# 17_-_PWR_IN_LEDS_BUTTONS_MECH.net
KiCad netlist of a schematic drawn in Altium Designer
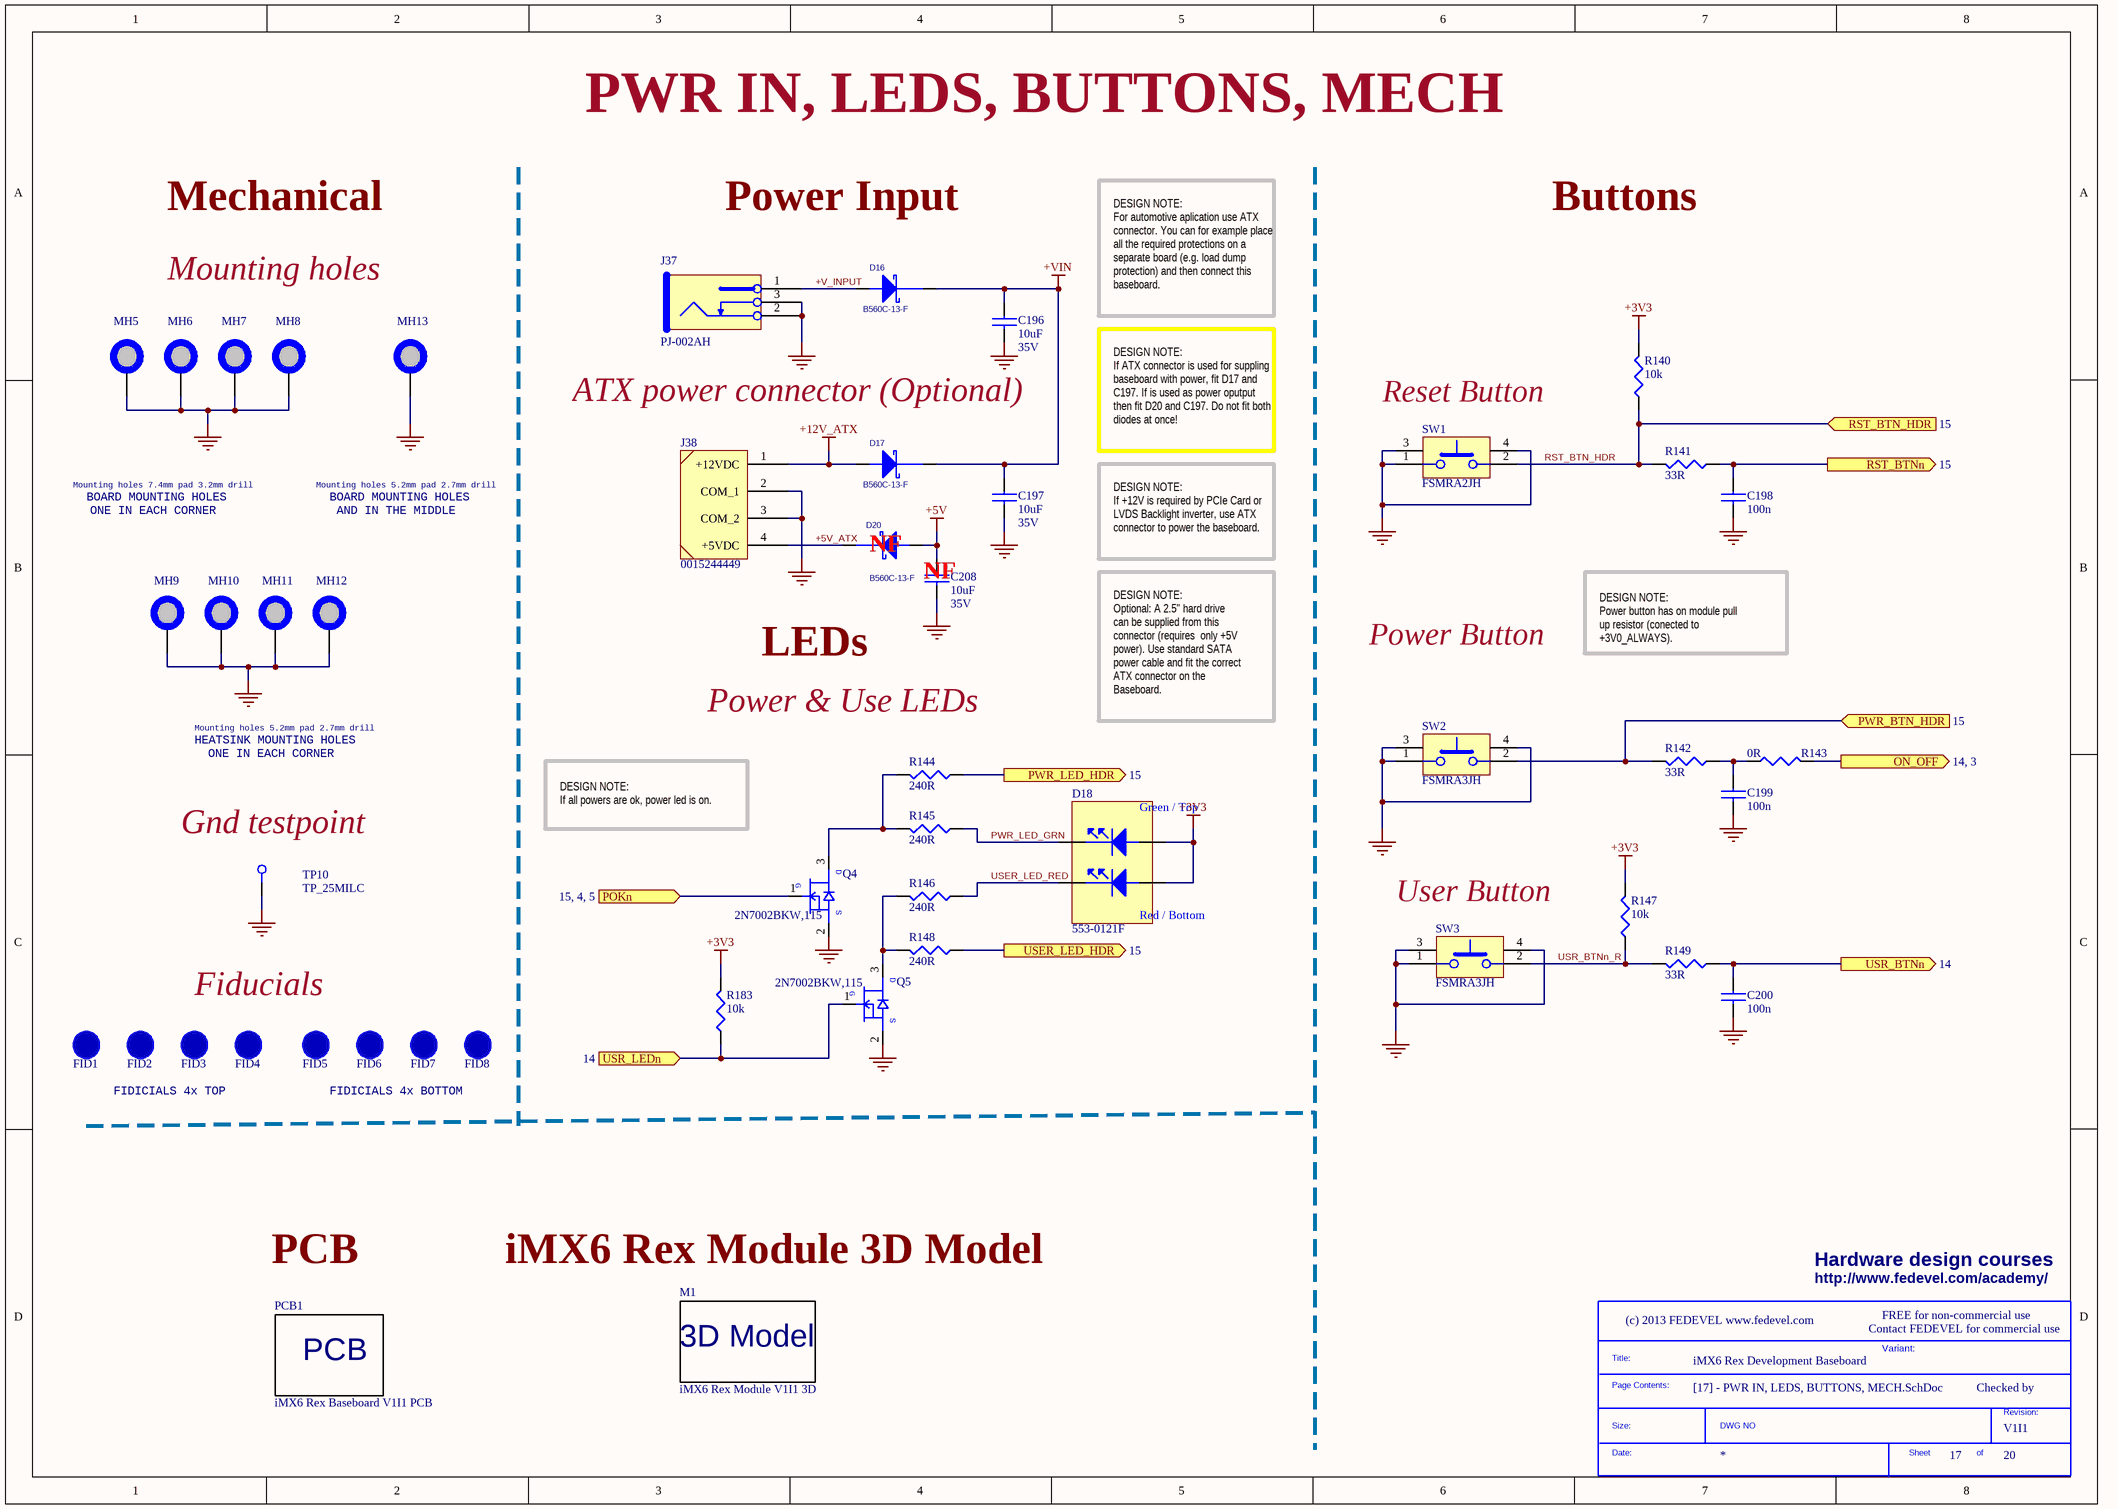
[diagram p0: [17] - PWR IN, LEDS, BUTTONS, MECH.SchDoc]

(export (version "E")
  (design (tool "Eeschema 10.0.6"))
  (components
    (comp (ref "C196")
      (value "10uF")
      (footprint "C1206")
      (description "CAP CER 10UF 35V X5R 1206")
      (fields
        (field (name "MANUFACTURER") "Murata Electronics North America")
        (field (name "MANUFACTURER PART NUMBER") "GRM31CR6YA106KA12L")
        (field (name "VOLTAGE - RATED") "35V")
      )
      (libsource (lib "Integrated_Library_RF_FEB_2012") (part "GRM31CR6YA106KA12L"))
    )
    (comp (ref "C197")
      (value "10uF")
      (footprint "C1206")
      (description "CAP CER 10UF 35V X5R 1206")
      (fields
        (field (name "MANUFACTURER") "Murata Electronics North America")
        (field (name "MANUFACTURER PART NUMBER") "GRM31CR6YA106KA12L")
        (field (name "VOLTAGE - RATED") "35V")
      )
      (libsource (lib "Integrated_Library_RF_FEB_2012") (part "GRM31CR6YA106KA12L"))
    )
    (comp (ref "C198")
      (value "100n")
      (footprint "C0402")
      (description "CAP CER .10UF 50V X5R 10% 0402")
      (fields
        (field (name "MANUFACTURER") "TDK Corporation")
        (field (name "MANUFACTURER PART NUMBER") "C1005X5R1H104K")
      )
      (libsource (lib "Integrated_Library_RF_FEB_2012") (part "C1005X5R1H104K"))
    )
    (comp (ref "C199")
      (value "100n")
      (footprint "C0402")
      (description "CAP CER .10UF 50V X5R 10% 0402")
      (fields
        (field (name "MANUFACTURER") "TDK Corporation")
        (field (name "MANUFACTURER PART NUMBER") "C1005X5R1H104K")
      )
      (libsource (lib "Integrated_Library_RF_FEB_2012") (part "C1005X5R1H104K"))
    )
    (comp (ref "C200")
      (value "100n")
      (footprint "C0402")
      (description "CAP CER .10UF 50V X5R 10% 0402")
      (fields
        (field (name "MANUFACTURER") "TDK Corporation")
        (field (name "MANUFACTURER PART NUMBER") "C1005X5R1H104K")
      )
      (libsource (lib "Integrated_Library_RF_FEB_2012") (part "C1005X5R1H104K"))
    )
    (comp (ref "C208")
      (value "10uF")
      (footprint "C1206")
      (description "CAP CER 10UF 35V X5R 1206")
      (fields
        (field (name "MANUFACTURER") "Murata Electronics North America")
        (field (name "MANUFACTURER PART NUMBER") "GRM31CR6YA106KA12L")
        (field (name "VOLTAGE - RATED") "35V")
      )
      (libsource (lib "Integrated_Library_RF_FEB_2012") (part "GRM31CR6YA106KA12L"))
    )
    (comp (ref "D16")
      (value "B560C-13-F")
      (footprint "SMC")
      (description "DIODE SCHOTTKY 60V 5A SMC")
      (fields (field (name "MANUFACTURER") "Diodes Inc"))
      (libsource (lib "Integrated_Library_RF_FEB_2012") (part "B560C-13-F"))
    )
    (comp (ref "D17")
      (value "B560C-13-F")
      (footprint "SMC")
      (description "DIODE SCHOTTKY 60V 5A SMC")
      (fields (field (name "MANUFACTURER") "Diodes Inc"))
      (libsource (lib "Integrated_Library_RF_FEB_2012") (part "B560C-13-F"))
    )
    (comp (ref "D18")
      (value "553-0121F")
      (footprint "553-0121F")
      (description "LED 2HI 3MM GREEN OVER RED PCMNT")
      (fields (field (name "MANUFACTURER") "Dialight"))
      (libsource (lib "Integrated_Library_RF_FEB_2012") (part "553-0121F"))
    )
    (comp (ref "D20")
      (value "B560C-13-F")
      (footprint "SMC")
      (description "DIODE SCHOTTKY 60V 5A SMC")
      (fields (field (name "MANUFACTURER") "Diodes Inc"))
      (libsource (lib "Integrated_Library_RF_FEB_2012") (part "B560C-13-F"))
    )
    (comp (ref "FID1")
      (value "FID_1MMC")
      (footprint "FID_40X120D")
      (description "Fiducial 40mil Diameter, 120mil Mask")
      (libsource (lib "Integrated_Library_RF_FEB_2012") (part "FID_1MMC"))
    )
    (comp (ref "FID2")
      (value "FID_1MMC")
      (footprint "FID_40X120D")
      (description "Fiducial 40mil Diameter, 120mil Mask")
      (libsource (lib "Integrated_Library_RF_FEB_2012") (part "FID_1MMC"))
    )
    (comp (ref "FID3")
      (value "FID_1MMC")
      (footprint "FID_40X120D")
      (description "Fiducial 40mil Diameter, 120mil Mask")
      (libsource (lib "Integrated_Library_RF_FEB_2012") (part "FID_1MMC"))
    )
    (comp (ref "FID4")
      (value "FID_1MMC")
      (footprint "FID_40X120D")
      (description "Fiducial 40mil Diameter, 120mil Mask")
      (libsource (lib "Integrated_Library_RF_FEB_2012") (part "FID_1MMC"))
    )
    (comp (ref "FID5")
      (value "FID_1MMC")
      (footprint "FID_40X120D")
      (description "Fiducial 40mil Diameter, 120mil Mask")
      (libsource (lib "Integrated_Library_RF_FEB_2012") (part "FID_1MMC"))
    )
    (comp (ref "FID6")
      (value "FID_1MMC")
      (footprint "FID_40X120D")
      (description "Fiducial 40mil Diameter, 120mil Mask")
      (libsource (lib "Integrated_Library_RF_FEB_2012") (part "FID_1MMC"))
    )
    (comp (ref "FID7")
      (value "FID_1MMC")
      (footprint "FID_40X120D")
      (description "Fiducial 40mil Diameter, 120mil Mask")
      (libsource (lib "Integrated_Library_RF_FEB_2012") (part "FID_1MMC"))
    )
    (comp (ref "FID8")
      (value "FID_1MMC")
      (footprint "FID_40X120D")
      (description "Fiducial 40mil Diameter, 120mil Mask")
      (libsource (lib "Integrated_Library_RF_FEB_2012") (part "FID_1MMC"))
    )
    (comp (ref "J37")
      (value "PJ-002AH")
      (footprint "POWER_JACK_5.5_2.1MM_NS")
      (description "CONN PWR JACK 2.1X5.5MM HIGH CUR")
      (fields (field (name "MANUFACTURER") "CUI Inc"))
      (libsource (lib "Integrated_Library_RF_FEB_2012") (part "PJ-002AH"))
    )
    (comp (ref "J38")
      (value "0015244449")
      (footprint "015244449")
      (description "CONN HEADER 4POS .200 VERT")
      (fields
        (field (name "MANUFACTURER") "Molex Inc")
        (field (name ".CREATOR") "MM")
        (field (name ".CHECKED PCB") "MM")
        (field (name ".CHECKED SCH") "MM")
      )
      (libsource (lib "Integrated_Library_RF_FEB_2012") (part "0015244449"))
    )
    (comp (ref "M1")
      (value "iMX6 Rex Module V1I1 3D")
      (footprint "iMX6 Rex Module 3D")
      (description "Printed Circuit Board")
      (fields (field (name ".CREATOR") "MM"))
      (libsource (lib "Integrated_Library_RF_FEB_2012") (part "3D_iMX6_REX_MODULE_V1I1"))
    )
    (comp (ref "MH5")
      (value "MH_7.4MMC_3.2MMD")
      (footprint "MH_7.4MMD_3.2MMD")
      (description "Mounting Hole 7.4mm Diameter, 3.2mm Drill")
      (libsource (lib "Integrated_Library_RF_FEB_2012") (part "MH_7.4MMC_3.2MMD"))
    )
    (comp (ref "MH6")
      (value "MH_7.4MMC_3.2MMD")
      (footprint "MH_7.4MMD_3.2MMD")
      (description "Mounting Hole 7.4mm Diameter, 3.2mm Drill")
      (libsource (lib "Integrated_Library_RF_FEB_2012") (part "MH_7.4MMC_3.2MMD"))
    )
    (comp (ref "MH7")
      (value "MH_7.4MMC_3.2MMD")
      (footprint "MH_7.4MMD_3.2MMD")
      (description "Mounting Hole 7.4mm Diameter, 3.2mm Drill")
      (libsource (lib "Integrated_Library_RF_FEB_2012") (part "MH_7.4MMC_3.2MMD"))
    )
    (comp (ref "MH8")
      (value "MH_7.4MMC_3.2MMD")
      (footprint "MH_7.4MMD_3.2MMD")
      (description "Mounting Hole 7.4mm Diameter, 3.2mm Drill")
      (libsource (lib "Integrated_Library_RF_FEB_2012") (part "MH_7.4MMC_3.2MMD"))
    )
    (comp (ref "MH9")
      (value "MH_5.2MMC_2.7MMD")
      (footprint "MH_5.2MMD_2.7MMD")
      (description "Mounting Hole 5.2mm Diameter, 2.7mm Drill")
      (fields (field (name ".CREATOR") "MM"))
      (libsource (lib "Integrated_Library_RF_FEB_2012") (part "MH_5.2MMC_2.7MMD"))
    )
    (comp (ref "MH10")
      (value "MH_5.2MMC_2.7MMD")
      (footprint "MH_5.2MMD_2.7MMD")
      (description "Mounting Hole 5.2mm Diameter, 2.7mm Drill")
      (fields (field (name ".CREATOR") "MM"))
      (libsource (lib "Integrated_Library_RF_FEB_2012") (part "MH_5.2MMC_2.7MMD"))
    )
    (comp (ref "MH11")
      (value "MH_5.2MMC_2.7MMD")
      (footprint "MH_5.2MMD_2.7MMD")
      (description "Mounting Hole 5.2mm Diameter, 2.7mm Drill")
      (fields (field (name ".CREATOR") "MM"))
      (libsource (lib "Integrated_Library_RF_FEB_2012") (part "MH_5.2MMC_2.7MMD"))
    )
    (comp (ref "MH12")
      (value "MH_5.2MMC_2.7MMD")
      (footprint "MH_5.2MMD_2.7MMD")
      (description "Mounting Hole 5.2mm Diameter, 2.7mm Drill")
      (fields (field (name ".CREATOR") "MM"))
      (libsource (lib "Integrated_Library_RF_FEB_2012") (part "MH_5.2MMC_2.7MMD"))
    )
    (comp (ref "MH13")
      (value "MH_5MMC_2.2MMD")
      (footprint "MH_5MMD_2.2MMD")
      (description "Mounting Hole 5mm Diameter, 2.2mm Drill")
      (libsource (lib "Integrated_Library_RF_FEB_2012") (part "MH_5MMC_2.2MMD"))
    )
    (comp (ref "PCB1")
      (value "iMX6 Rex Baseboard V1I1 PCB")
      (description "Printed Circuit Board")
      (fields (field (name ".CREATOR") "MM") (field (name ".CHECKED SCH") "MM"))
      (libsource (lib "Integrated_Library_RF_FEB_2012") (part "PCB_iMX6_REX_Baseboard_V1I1"))
    )
    (comp (ref "Q4")
      (value "2N7002BKW,115")
      (footprint "SC70_SOT323")
      (description "MOSFET N-CH 60V 310MA SOT323")
      (fields
        (field (name "MANUFACTURER") "NXP Semiconductors")
        (field (name ".CHECKED PCB") "RF")
        (field (name ".CHECKED SCH") "RF")
      )
      (libsource (lib "Integrated_Library_RF_FEB_2012") (part "2N7002BKW,115"))
    )
    (comp (ref "Q5")
      (value "2N7002BKW,115")
      (footprint "SC70_SOT323")
      (description "MOSFET N-CH 60V 310MA SOT323")
      (fields
        (field (name "MANUFACTURER") "NXP Semiconductors")
        (field (name ".CHECKED PCB") "RF")
        (field (name ".CHECKED SCH") "RF")
      )
      (libsource (lib "Integrated_Library_RF_FEB_2012") (part "2N7002BKW,115"))
    )
    (comp (ref "R140")
      (value "10k")
      (footprint "R0402")
      (description "RES 10.0K OHM 1/16W 1% 0402 SMD")
      (fields
        (field (name "MANUFACTURER") "Yageo")
        (field (name "MANUFACTURER PART NUMBER") "RC0402FR-0710KL")
      )
      (libsource (lib "Integrated_Library_RF_FEB_2012") (part "RC0402FR-0710KL"))
    )
    (comp (ref "R141")
      (value "33R")
      (footprint "R0402")
      (description "RES TF 33 OHM 1% 1/16W 0402")
      (fields
        (field (name "MANUFACTURER") "Stackpole Electronics Inc")
        (field (name "MANUFACTURER PART NUMBER") "RMCF0402FT33R0")
        (field (name ".CHECKED PCB") "RF")
        (field (name ".CHECKED SCH") "RF")
      )
      (libsource (lib "Integrated_Library_RF_FEB_2012") (part "RMCF0402FT33R0"))
    )
    (comp (ref "R142")
      (value "33R")
      (footprint "R0402")
      (description "RES TF 33 OHM 1% 1/16W 0402")
      (fields
        (field (name "MANUFACTURER") "Stackpole Electronics Inc")
        (field (name "MANUFACTURER PART NUMBER") "RMCF0402FT33R0")
        (field (name ".CHECKED PCB") "RF")
        (field (name ".CHECKED SCH") "RF")
      )
      (libsource (lib "Integrated_Library_RF_FEB_2012") (part "RMCF0402FT33R0"))
    )
    (comp (ref "R143")
      (value "0R")
      (footprint "R0402")
      (description "RES 0.0 OHM 1/16W 0402 SMD")
      (fields
        (field (name "MANUFACTURER") "Yageo")
        (field (name "MANUFACTURER PART NUMBER") "RC0402JR-070RL")
      )
      (libsource (lib "Integrated_Library_RF_FEB_2012") (part "RC0402JR-070RL"))
    )
    (comp (ref "R144")
      (value "240R")
      (footprint "R0402")
      (description "RES TF 240 OHM 1% 0.0625W 0402")
      (fields
        (field (name "MANUFACTURER") "Stackpole Electronics Inc")
        (field (name "MANUFACTURER PART NUMBER") "RMCF0402FT240R")
      )
      (libsource (lib "Integrated_Library_RF_FEB_2012") (part "RMCF0402FT240R"))
    )
    (comp (ref "R145")
      (value "240R")
      (footprint "R0402")
      (description "RES TF 240 OHM 1% 0.0625W 0402")
      (fields
        (field (name "MANUFACTURER") "Stackpole Electronics Inc")
        (field (name "MANUFACTURER PART NUMBER") "RMCF0402FT240R")
      )
      (libsource (lib "Integrated_Library_RF_FEB_2012") (part "RMCF0402FT240R"))
    )
    (comp (ref "R146")
      (value "240R")
      (footprint "R0402")
      (description "RES TF 240 OHM 1% 0.0625W 0402")
      (fields
        (field (name "MANUFACTURER") "Stackpole Electronics Inc")
        (field (name "MANUFACTURER PART NUMBER") "RMCF0402FT240R")
      )
      (libsource (lib "Integrated_Library_RF_FEB_2012") (part "RMCF0402FT240R"))
    )
    (comp (ref "R147")
      (value "10k")
      (footprint "R0402")
      (description "RES 10.0K OHM 1/16W 1% 0402 SMD")
      (fields
        (field (name "MANUFACTURER") "Yageo")
        (field (name "MANUFACTURER PART NUMBER") "RC0402FR-0710KL")
      )
      (libsource (lib "Integrated_Library_RF_FEB_2012") (part "RC0402FR-0710KL"))
    )
    (comp (ref "R148")
      (value "240R")
      (footprint "R0402")
      (description "RES TF 240 OHM 1% 0.0625W 0402")
      (fields
        (field (name "MANUFACTURER") "Stackpole Electronics Inc")
        (field (name "MANUFACTURER PART NUMBER") "RMCF0402FT240R")
      )
      (libsource (lib "Integrated_Library_RF_FEB_2012") (part "RMCF0402FT240R"))
    )
    (comp (ref "R149")
      (value "33R")
      (footprint "R0402")
      (description "RES TF 33 OHM 1% 1/16W 0402")
      (fields
        (field (name "MANUFACTURER") "Stackpole Electronics Inc")
        (field (name "MANUFACTURER PART NUMBER") "RMCF0402FT33R0")
        (field (name ".CHECKED PCB") "RF")
        (field (name ".CHECKED SCH") "RF")
      )
      (libsource (lib "Integrated_Library_RF_FEB_2012") (part "RMCF0402FT33R0"))
    )
    (comp (ref "R183")
      (value "10k")
      (footprint "R0402")
      (description "RES 10.0K OHM 1/16W 1% 0402 SMD")
      (fields
        (field (name "MANUFACTURER") "Yageo")
        (field (name "MANUFACTURER PART NUMBER") "RC0402FR-0710KL")
      )
      (libsource (lib "Integrated_Library_RF_FEB_2012") (part "RC0402FR-0710KL"))
    )
    (comp (ref "SW1")
      (value "FSMRA2JH")
      (footprint "FSMRA2JH")
      (description "SWITCH TACTILE SPST-NO 0.05A 12V")
      (fields
        (field (name "MANUFACTURER") "TE Connectivity")
        (field (name ".CREATOR") "MM")
        (field (name ".CHECKED PCB") "MM")
        (field (name ".CHECKED SCH") "MM")
      )
      (libsource (lib "Integrated_Library_RF_FEB_2012") (part "FSMRA2JH"))
    )
    (comp (ref "SW2")
      (value "FSMRA3JH")
      (footprint "FSMRA3JH")
      (description "SWITCH TACTILE SPST-NO 0.05A 12V")
      (fields
        (field (name "MANUFACTURER") "TE Connectivity")
        (field (name ".CREATOR") "MM")
        (field (name ".CHECKED PCB") "MM")
        (field (name ".CHECKED SCH") "MM")
      )
      (libsource (lib "Integrated_Library_RF_FEB_2012") (part "FSMRA3JH"))
    )
    (comp (ref "SW3")
      (value "FSMRA3JH")
      (footprint "FSMRA3JH")
      (description "SWITCH TACTILE SPST-NO 0.05A 12V")
      (fields
        (field (name "MANUFACTURER") "TE Connectivity")
        (field (name ".CREATOR") "MM")
        (field (name ".CHECKED PCB") "MM")
        (field (name ".CHECKED SCH") "MM")
      )
      (libsource (lib "Integrated_Library_RF_FEB_2012") (part "FSMRA3JH"))
    )
    (comp (ref "TP10")
      (value "TP_25MILC")
      (footprint "TP_25C")
      (description "Test Point 25mil")
      (libsource (lib "Integrated_Library_RF_FEB_2012") (part "TP_25MILC"))
    )
  )
  (nets
    (net (code "1") (name "+3V3") (class "Default")
      (node (ref "D18") (pin "2") (pinfunction "ANODE_2") (pintype "passive"))
      (node (ref "D18") (pin "4") (pinfunction "ANODE_4") (pintype "passive"))
      (node (ref "R140") (pin "2") (pinfunction "2_2") (pintype "passive"))
      (node (ref "R147") (pin "2") (pinfunction "2_2") (pintype "passive"))
      (node (ref "R183") (pin "2") (pinfunction "2_2") (pintype "passive"))
    )
    (net (code "2") (name "+5V") (class "Default")
      (node (ref "C208") (pin "1") (pinfunction "1_1") (pintype "passive"))
      (node (ref "D20") (pin "2") (pinfunction "ANODE_2") (pintype "passive"))
    )
    (net (code "3") (name "+12V_ATX") (class "Default")
      (node (ref "D17") (pin "2") (pinfunction "ANODE_2") (pintype "passive"))
      (node (ref "J38") (pin "1") (pinfunction "+12VDC_1") (pintype "passive"))
    )
    (net (code "4") (name "+VIN") (class "Default")
      (node (ref "C196") (pin "1") (pinfunction "1_1") (pintype "passive"))
      (node (ref "C197") (pin "1") (pinfunction "1_1") (pintype "passive"))
      (node (ref "D16") (pin "1") (pinfunction "cathode_1") (pintype "passive"))
      (node (ref "D17") (pin "1") (pinfunction "cathode_1") (pintype "passive"))
    )
    (net (code "5") (name "/+5V_ATX") (class "Default")
      (node (ref "D20") (pin "1") (pinfunction "cathode_1") (pintype "passive"))
      (node (ref "J38") (pin "4") (pinfunction "+5VDC_4") (pintype "passive"))
    )
    (net (code "6") (name "/+V_INPUT") (class "Default")
      (node (ref "D16") (pin "2") (pinfunction "ANODE_2") (pintype "passive"))
      (node (ref "J37") (pin "1") (pinfunction "1_1") (pintype "passive"))
    )
    (net (code "7") (name "/ON_OFF") (class "Default")
      (node (ref "R143") (pin "2") (pinfunction "2_2") (pintype "passive"))
    )
    (net (code "8") (name "/POKn") (class "Default")
      (node (ref "Q4") (pin "1") (pinfunction "GATE_1") (pintype "passive"))
    )
    (net (code "9") (name "/PWR_BTN_HDR") (class "Default")
      (node (ref "R142") (pin "2") (pinfunction "2_2") (pintype "passive"))
      (node (ref "SW2") (pin "2") (pinfunction "2_2") (pintype "passive"))
    )
    (net (code "10") (name "/PWR_LED_GRN") (class "Default")
      (node (ref "D18") (pin "3") (pinfunction "cathode_3") (pintype "passive"))
      (node (ref "R145") (pin "1") (pinfunction "1_1") (pintype "passive"))
    )
    (net (code "11") (name "/PWR_LED_HDR") (class "Default")
      (node (ref "R144") (pin "1") (pinfunction "1_1") (pintype "passive"))
    )
    (net (code "12") (name "/RST_BTN_HDR") (class "Default")
      (node (ref "R140") (pin "1") (pinfunction "1_1") (pintype "passive"))
      (node (ref "R141") (pin "2") (pinfunction "2_2") (pintype "passive"))
      (node (ref "SW1") (pin "2") (pinfunction "2_2") (pintype "passive"))
    )
    (net (code "13") (name "/RST_BTNn") (class "Default")
      (node (ref "C198") (pin "1") (pinfunction "1_1") (pintype "passive"))
      (node (ref "R141") (pin "1") (pinfunction "1_1") (pintype "passive"))
    )
    (net (code "14") (name "/USER_LED_HDR") (class "Default")
      (node (ref "R148") (pin "1") (pinfunction "1_1") (pintype "passive"))
    )
    (net (code "15") (name "/USER_LED_RED") (class "Default")
      (node (ref "D18") (pin "1") (pinfunction "cathode_1") (pintype "passive"))
      (node (ref "R146") (pin "1") (pinfunction "1_1") (pintype "passive"))
    )
    (net (code "16") (name "/USR_BTNn") (class "Default")
      (node (ref "C200") (pin "1") (pinfunction "1_1") (pintype "passive"))
      (node (ref "R149") (pin "1") (pinfunction "1_1") (pintype "passive"))
    )
    (net (code "17") (name "/USR_BTNn_R") (class "Default")
      (node (ref "R147") (pin "1") (pinfunction "1_1") (pintype "passive"))
      (node (ref "R149") (pin "2") (pinfunction "2_2") (pintype "passive"))
      (node (ref "SW3") (pin "2") (pinfunction "2_2") (pintype "passive"))
    )
    (net (code "18") (name "/USR_LEDn") (class "Default")
      (node (ref "Q5") (pin "1") (pinfunction "GATE_1") (pintype "passive"))
      (node (ref "R183") (pin "1") (pinfunction "1_1") (pintype "passive"))
    )
    (net (code "19") (name "GND") (class "Default")
      (node (ref "C196") (pin "2") (pinfunction "2_2") (pintype "passive"))
      (node (ref "C197") (pin "2") (pinfunction "2_2") (pintype "passive"))
      (node (ref "C198") (pin "2") (pinfunction "2_2") (pintype "passive"))
      (node (ref "C199") (pin "2") (pinfunction "2_2") (pintype "passive"))
      (node (ref "C200") (pin "2") (pinfunction "2_2") (pintype "passive"))
      (node (ref "C208") (pin "2") (pinfunction "2_2") (pintype "passive"))
      (node (ref "J37") (pin "2") (pinfunction "2_2") (pintype "passive"))
      (node (ref "J37") (pin "3") (pinfunction "3_3") (pintype "passive"))
      (node (ref "J38") (pin "2") (pinfunction "COM_1_2") (pintype "passive"))
      (node (ref "J38") (pin "3") (pinfunction "COM_2_3") (pintype "passive"))
      (node (ref "MH10") (pin "1") (pinfunction "1_1") (pintype "passive"))
      (node (ref "MH11") (pin "1") (pinfunction "1_1") (pintype "passive"))
      (node (ref "MH12") (pin "1") (pinfunction "1_1") (pintype "passive"))
      (node (ref "MH13") (pin "1") (pinfunction "1_1") (pintype "passive"))
      (node (ref "MH5") (pin "1") (pinfunction "1_1") (pintype "passive"))
      (node (ref "MH6") (pin "1") (pinfunction "1_1") (pintype "passive"))
      (node (ref "MH7") (pin "1") (pinfunction "1_1") (pintype "passive"))
      (node (ref "MH8") (pin "1") (pinfunction "1_1") (pintype "passive"))
      (node (ref "MH9") (pin "1") (pinfunction "1_1") (pintype "passive"))
      (node (ref "Q4") (pin "2") (pinfunction "SOURCE_2") (pintype "passive"))
      (node (ref "Q5") (pin "2") (pinfunction "SOURCE_2") (pintype "passive"))
      (node (ref "SW1") (pin "1") (pinfunction "1_1") (pintype "passive"))
      (node (ref "SW1") (pin "3") (pinfunction "MECH1_3") (pintype "passive"))
      (node (ref "SW1") (pin "4") (pinfunction "MECH2_4") (pintype "passive"))
      (node (ref "SW2") (pin "1") (pinfunction "1_1") (pintype "passive"))
      (node (ref "SW2") (pin "3") (pinfunction "MECH1_3") (pintype "passive"))
      (node (ref "SW2") (pin "4") (pinfunction "MECH2_4") (pintype "passive"))
      (node (ref "SW3") (pin "1") (pinfunction "1_1") (pintype "passive"))
      (node (ref "SW3") (pin "3") (pinfunction "MECH1_3") (pintype "passive"))
      (node (ref "SW3") (pin "4") (pinfunction "MECH2_4") (pintype "passive"))
      (node (ref "TP10") (pin "1") (pinfunction "1_1") (pintype "passive"))
    )
    (net (code "20") (name "Net-(C199-Pad1)") (class "Default")
      (node (ref "C199") (pin "1") (pinfunction "1_1") (pintype "passive"))
      (node (ref "R142") (pin "1") (pinfunction "1_1") (pintype "passive"))
      (node (ref "R143") (pin "1") (pinfunction "1_1") (pintype "passive"))
    )
    (net (code "21") (name "Net-(Q4-DRAIN)") (class "Default")
      (node (ref "Q4") (pin "3") (pinfunction "DRAIN_3") (pintype "passive"))
      (node (ref "R144") (pin "2") (pinfunction "2_2") (pintype "passive"))
      (node (ref "R145") (pin "2") (pinfunction "2_2") (pintype "passive"))
    )
    (net (code "22") (name "Net-(Q5-DRAIN)") (class "Default")
      (node (ref "Q5") (pin "3") (pinfunction "DRAIN_3") (pintype "passive"))
      (node (ref "R146") (pin "2") (pinfunction "2_2") (pintype "passive"))
      (node (ref "R148") (pin "2") (pinfunction "2_2") (pintype "passive"))
    )
  )
)
